# subckt_adjustable_LDO.net
KiCad netlist of a schematic drawn in Altium Designer
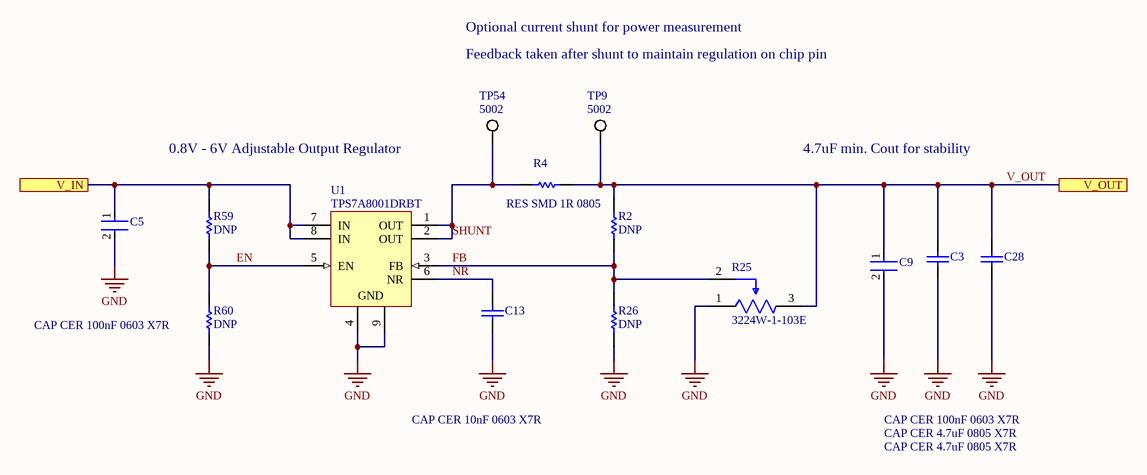
[diagram p0: subckt_adjustable_LDO.SchDoc]

(export (version "E")
  (design (tool "Eeschema 10.0.6"))
  (components
    (comp (ref "C3")
      (value "CAP CER 4.7uF 0805 X7R")
      (footprint "CAPC2013X140X50NL20T25")
      (fields
        (field (name "PART NUMBER") "0805ZC475KAT2A")
        (field (name "MANUFACTURER") "AVX Interconnect / Elco")
      )
      (libsource (lib "Altium Content Vault") (part "CAP"))
    )
    (comp (ref "C5")
      (value "CAP CER 100nF 0603 X7R")
      (footprint "FP-CC0603-DA-MFG")
      (description "CAP CER 0.1UF 16V X7R 0603")
      (fields
        (field (name "OCTOPART") "https://octopart.com/cc0603krx7r7bb104-yageo-192941")
        (field (name "TOLERANCE") "0.1")
      )
      (libsource (lib "Altium Content Vault") (part "11868f565c42a9108669ba33697ecf6"))
    )
    (comp (ref "C9")
      (value "CAP CER 100nF 0603 X7R")
      (footprint "FP-CC0603-DA-MFG")
      (description "CAP CER 0.1UF 16V X7R 0603")
      (fields
        (field (name "OCTOPART") "https://octopart.com/cc0603krx7r7bb104-yageo-192941")
        (field (name "TOLERANCE") "0.1")
      )
      (libsource (lib "Altium Content Vault") (part "11868f565c42a9108669ba33697ecf6"))
    )
    (comp (ref "C13")
      (value "CAP CER 10nF 0603 X7R")
      (footprint "CAPC1608X90X40ML10T20")
      (description "Chip Capacitor, 10 nF, +/- 10%, 50 V, -55 to 125 degC, 0603 (1608 Metric), RoHS, Tape and Reel")
      (fields (field (name "MANUFACTURER") "Yageo") (field (name "TOLERANCE") "10%"))
      (libsource (lib "Altium Content Vault") (part "CAP-NP-2"))
    )
    (comp (ref "C28")
      (value "CAP CER 4.7uF 0805 X7R")
      (footprint "CAPC2013X140X50NL20T25")
      (fields
        (field (name "PART NUMBER") "0805ZC475KAT2A")
        (field (name "MANUFACTURER") "AVX Interconnect / Elco")
      )
      (libsource (lib "Altium Content Vault") (part "CAP"))
    )
    (comp (ref "R2")
      (value "DNP")
      (footprint "RESC1609X50X30LL10T20")
      (fields (field (name "PART NUMBER") "CRCW0603100KFKEA") (field (name "MANUFACTURER") "Vishay Dale"))
      (libsource (lib "Altium Content Vault") (part "RES"))
    )
    (comp (ref "R4")
      (value "RES SMD 1R 0805")
      (footprint "RESC2013X50X30NL20T20")
      (fields (field (name "MANUFACTURER") "Vishay Dale") (field (name "PART NUMBER") "CRCW08050000Z0EB"))
      (libsource (lib "Altium Content Vault") (part "RES"))
    )
    (comp (ref "R25")
      (value "3224W-1-103E")
      (footprint "FP-3224W-MFG")
      (description "TRIMMER 10K OHM 0.25W J LEAD TOP")
      (fields (field (name "TOLERANCE") "10%") (field (name "MANUFACTURER") "Bourns"))
      (libsource (lib "Altium Content Vault") (part "83d3d349ed884d1db45cec512f27eb6"))
    )
    (comp (ref "R26")
      (value "DNP")
      (footprint "RESC1609X50X30LL10T20")
      (fields (field (name "PART NUMBER") "CRCW0603100KFKEA") (field (name "MANUFACTURER") "Vishay Dale"))
      (libsource (lib "Altium Content Vault") (part "RES"))
    )
    (comp (ref "R59")
      (value "DNP")
      (footprint "RESC1609X50X30LL10T20")
      (fields (field (name "PART NUMBER") "CRCW0603100KFKEA") (field (name "MANUFACTURER") "Vishay Dale"))
      (libsource (lib "Altium Content Vault") (part "RES"))
    )
    (comp (ref "R60")
      (value "DNP")
      (footprint "RESC1609X50X30LL10T20")
      (fields (field (name "PART NUMBER") "CRCW0603100KFKEA") (field (name "MANUFACTURER") "Vishay Dale"))
      (libsource (lib "Altium Content Vault") (part "RES"))
    )
    (comp (ref "TP9")
      (value "5002")
      (footprint "KSTN-5002")
      (description "Test Point, White, 1-Pin THD, RoHS, Bulk")
      (fields (field (name "MANUFACTURER") "KeystoneElectronics"))
      (libsource (lib "Altium Content Vault") (part "KSTN-TP-5002"))
    )
    (comp (ref "TP54")
      (value "5002")
      (footprint "KSTN-5002")
      (description "Test Point, White, 1-Pin THD, RoHS, Bulk")
      (fields (field (name "MANUFACTURER") "KeystoneElectronics"))
      (libsource (lib "Altium Content Vault") (part "KSTN-TP-5002"))
    )
    (comp (ref "U1")
      (value "TPS7A8001DRBT")
      (footprint "DRB0008A_V")
      (fields (field (name "MANUFACTURER") "Texas Instruments"))
      (libsource (lib "Altium Content Vault") (part "TI-TPS7A8X01DRB8-1750X1500TP"))
    )
  )
  (nets
    (net (code "1") (name "/EN") (class "Default")
      (node (ref "R59") (pin "1") (pinfunction "1_1") (pintype "passive"))
      (node (ref "R60") (pin "2") (pinfunction "2_2") (pintype "passive"))
      (node (ref "U1") (pin "5") (pinfunction "EN_5") (pintype "input"))
    )
    (net (code "2") (name "/FB") (class "Default")
      (node (ref "R2") (pin "1") (pinfunction "1_1") (pintype "passive"))
      (node (ref "R25") (pin "2") (pinfunction "WIPER_2") (pintype "passive"))
      (node (ref "R26") (pin "2") (pinfunction "2_2") (pintype "passive"))
      (node (ref "U1") (pin "3") (pinfunction "FB_3") (pintype "input"))
    )
    (net (code "3") (name "/NR") (class "Default")
      (node (ref "C13") (pin "1") (pinfunction "1_1") (pintype "passive"))
      (node (ref "U1") (pin "6") (pinfunction "NR_6") (pintype "passive"))
    )
    (net (code "4") (name "/SHUNT") (class "Default")
      (node (ref "R4") (pin "1") (pinfunction "1_1") (pintype "passive"))
      (node (ref "TP54") (pin "1") (pintype "passive"))
      (node (ref "U1") (pin "1") (pinfunction "OUT_1") (pintype "power_in"))
      (node (ref "U1") (pin "2") (pinfunction "OUT_2") (pintype "power_in"))
    )
    (net (code "5") (name "/V_IN") (class "Default")
      (node (ref "C5") (pin "1") (pinfunction "1_1") (pintype "passive"))
      (node (ref "R59") (pin "2") (pinfunction "2_2") (pintype "passive"))
      (node (ref "U1") (pin "7") (pinfunction "IN_7") (pintype "power_in"))
      (node (ref "U1") (pin "8") (pinfunction "IN_8") (pintype "power_in"))
    )
    (net (code "6") (name "/V_OUT") (class "Default")
      (node (ref "C28") (pin "1") (pinfunction "1_1") (pintype "passive"))
      (node (ref "C3") (pin "1") (pinfunction "1_1") (pintype "passive"))
      (node (ref "C9") (pin "1") (pinfunction "1_1") (pintype "passive"))
      (node (ref "R2") (pin "2") (pinfunction "2_2") (pintype "passive"))
      (node (ref "R25") (pin "3") (pinfunction "CW_3") (pintype "passive"))
      (node (ref "R4") (pin "2") (pinfunction "2_2") (pintype "passive"))
      (node (ref "TP9") (pin "1") (pintype "passive"))
    )
    (net (code "7") (name "GND") (class "Default")
      (node (ref "C13") (pin "2") (pinfunction "2_2") (pintype "passive"))
      (node (ref "C28") (pin "2") (pinfunction "2_2") (pintype "passive"))
      (node (ref "C3") (pin "2") (pinfunction "2_2") (pintype "passive"))
      (node (ref "C5") (pin "2") (pinfunction "2_2") (pintype "passive"))
      (node (ref "C9") (pin "2") (pinfunction "2_2") (pintype "passive"))
      (node (ref "R25") (pin "1") (pinfunction "CCW_1") (pintype "passive"))
      (node (ref "R26") (pin "1") (pinfunction "1_1") (pintype "passive"))
      (node (ref "R60") (pin "1") (pinfunction "1_1") (pintype "passive"))
      (node (ref "U1") (pin "4") (pinfunction "GND_4") (pintype "power_in"))
      (node (ref "U1") (pin "9") (pinfunction "GND_9") (pintype "power_in"))
    )
  )
)
